# 03_-_CONTROLLER.net
KiCad netlist of a schematic drawn in Altium Designer
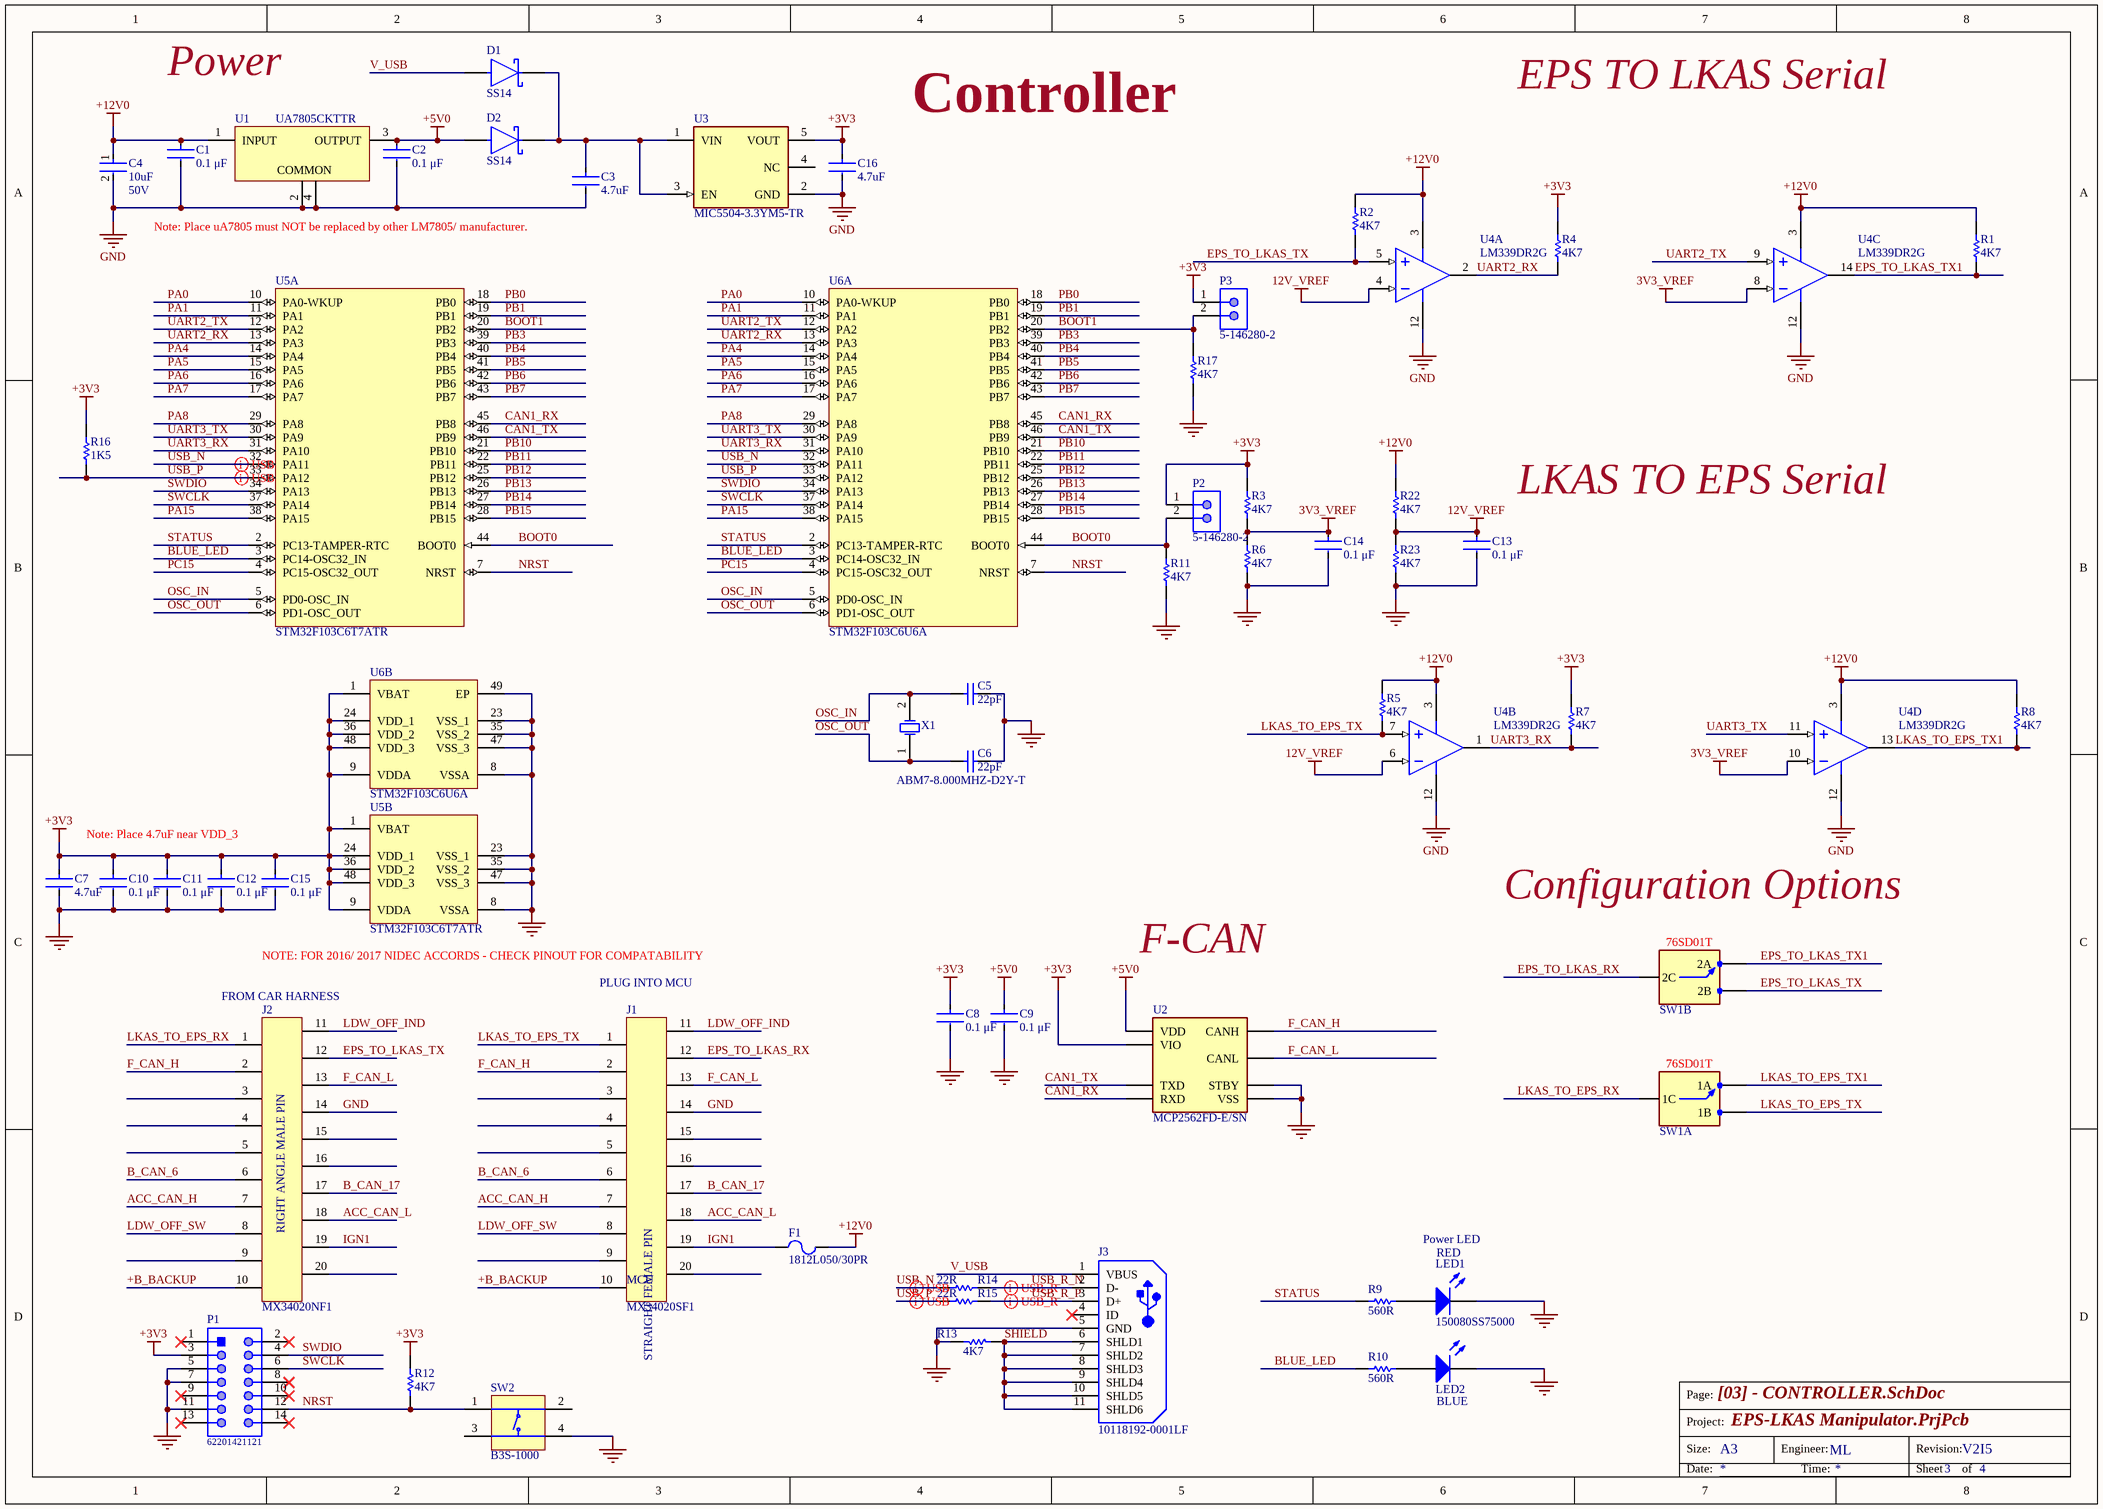
[diagram p0: [03] - CONTROLLER.SchDoc]

(export (version "E")
  (design (tool "Eeschema 10.0.6"))
  (components
    (comp (ref "C1")
      (value "C0603C104M3RACTU")
      (footprint "FP-C0603C-CF-MFG")
      (description "CAP CER 0.1UF 25V X7R 0603")
      (fields
        (field (name "CAPACITANCE") "0.1 μF")
        (field (name "OCTOPART") "https://octopart.com/c0603c104m3ractu-kemet-95914")
        (field (name "MANUFACTURER") "KEMET")
      )
      (libsource (lib "Altium Content Vault") (part "b4654b650e69147ec39a6b967a45e02"))
    )
    (comp (ref "C2")
      (value "C0603C104M3RACTU")
      (footprint "FP-C0603C-CF-MFG")
      (description "CAP CER 0.1UF 25V X7R 0603")
      (fields
        (field (name "CAPACITANCE") "0.1 μF")
        (field (name "OCTOPART") "https://octopart.com/c0603c104m3ractu-kemet-95914")
        (field (name "MANUFACTURER") "KEMET")
      )
      (libsource (lib "Altium Content Vault") (part "b4654b650e69147ec39a6b967a45e02"))
    )
    (comp (ref "C3")
      (value "CL10B475KQ8NQNC")
      (footprint "FP-CL10-IPC_C")
      (description "CAP CER 4.7UF 6.3V X7R 0603")
      (fields
        (field (name "TOLERANCE") "10%")
        (field (name "CAPACITANCE") "4.7uF")
        (field (name "OCTOPART") "https://octopart.com/cl10b475kq8nqnc-samsung-24957976")
      )
      (libsource (lib "") (part "11868f565c42a9108669ba33697ecf6_1"))
    )
    (comp (ref "C4")
      (value "10uF")
      (footprint "FP-CL31-IPC_C")
      (description "CAP CER 10UF 50V X5R 1206")
      (fields
        (field (name "TOLERANCE") "10%")
        (field (name "MANUFACTURER") "Samsung")
        (field (name "VOLTAGE") "50V")
      )
      (libsource (lib "Altium Content Vault") (part "11868f565c42a9108669ba33697ecf6"))
    )
    (comp (ref "C5")
      (value "GRM1885C1H220JA01D")
      (footprint "CAPC1608X90X35ML10T15")
      (description "Chip Capacitor, 22 pF, +/- 5%, 50 V, -55 to 125 degC, 0603 (1608 Metric), RoHS, Tape and Reel")
      (fields (field (name "CAPACITANCE") "22pF") (field (name "MANUFACTURER") "Murata"))
      (libsource (lib "Altium Content Vault") (part "CAP-NP-2"))
    )
    (comp (ref "C6")
      (value "GRM1885C1H220JA01D")
      (footprint "CAPC1608X90X35ML10T15")
      (description "Chip Capacitor, 22 pF, +/- 5%, 50 V, -55 to 125 degC, 0603 (1608 Metric), RoHS, Tape and Reel")
      (fields (field (name "CAPACITANCE") "22pF") (field (name "MANUFACTURER") "Murata"))
      (libsource (lib "Altium Content Vault") (part "CAP-NP-2"))
    )
    (comp (ref "C7")
      (value "CL10B475KQ8NQNC")
      (footprint "FP-CL10-IPC_C")
      (description "CAP CER 4.7UF 6.3V X7R 0603")
      (fields
        (field (name "TOLERANCE") "10%")
        (field (name "CAPACITANCE") "4.7uF")
        (field (name "OCTOPART") "https://octopart.com/cl10b475kq8nqnc-samsung-24957976")
      )
      (libsource (lib "") (part "11868f565c42a9108669ba33697ecf6_1"))
    )
    (comp (ref "C8")
      (value "C0603C104M3RACTU")
      (footprint "FP-C0603C-CF-MFG")
      (description "CAP CER 0.1UF 25V X7R 0603")
      (fields
        (field (name "CAPACITANCE") "0.1 μF")
        (field (name "OCTOPART") "https://octopart.com/c0603c104m3ractu-kemet-95914")
        (field (name "MANUFACTURER") "KEMET")
      )
      (libsource (lib "Altium Content Vault") (part "b4654b650e69147ec39a6b967a45e02"))
    )
    (comp (ref "C9")
      (value "C0603C104M3RACTU")
      (footprint "FP-C0603C-CF-MFG")
      (description "CAP CER 0.1UF 25V X7R 0603")
      (fields
        (field (name "CAPACITANCE") "0.1 μF")
        (field (name "OCTOPART") "https://octopart.com/c0603c104m3ractu-kemet-95914")
        (field (name "MANUFACTURER") "KEMET")
      )
      (libsource (lib "Altium Content Vault") (part "b4654b650e69147ec39a6b967a45e02"))
    )
    (comp (ref "C10")
      (value "C0603C104M3RACTU")
      (footprint "FP-C0603C-CF-MFG")
      (description "CAP CER 0.1UF 25V X7R 0603")
      (fields
        (field (name "CAPACITANCE") "0.1 μF")
        (field (name "OCTOPART") "https://octopart.com/c0603c104m3ractu-kemet-95914")
        (field (name "MANUFACTURER") "KEMET")
      )
      (libsource (lib "Altium Content Vault") (part "b4654b650e69147ec39a6b967a45e02"))
    )
    (comp (ref "C11")
      (value "C0603C104M3RACTU")
      (footprint "FP-C0603C-CF-MFG")
      (description "CAP CER 0.1UF 25V X7R 0603")
      (fields
        (field (name "CAPACITANCE") "0.1 μF")
        (field (name "OCTOPART") "https://octopart.com/c0603c104m3ractu-kemet-95914")
        (field (name "MANUFACTURER") "KEMET")
      )
      (libsource (lib "Altium Content Vault") (part "b4654b650e69147ec39a6b967a45e02"))
    )
    (comp (ref "C12")
      (value "C0603C104M3RACTU")
      (footprint "FP-C0603C-CF-MFG")
      (description "CAP CER 0.1UF 25V X7R 0603")
      (fields
        (field (name "CAPACITANCE") "0.1 μF")
        (field (name "OCTOPART") "https://octopart.com/c0603c104m3ractu-kemet-95914")
        (field (name "MANUFACTURER") "KEMET")
      )
      (libsource (lib "Altium Content Vault") (part "b4654b650e69147ec39a6b967a45e02"))
    )
    (comp (ref "C13")
      (value "C0603C104M3RACTU")
      (footprint "FP-C0603C-CF-MFG")
      (description "CAP CER 0.1UF 25V X7R 0603")
      (fields
        (field (name "CAPACITANCE") "0.1 μF")
        (field (name "OCTOPART") "https://octopart.com/c0603c104m3ractu-kemet-95914")
        (field (name "MANUFACTURER") "KEMET")
      )
      (libsource (lib "Altium Content Vault") (part "b4654b650e69147ec39a6b967a45e02"))
    )
    (comp (ref "C14")
      (value "C0603C104M3RACTU")
      (footprint "FP-C0603C-CF-MFG")
      (description "CAP CER 0.1UF 25V X7R 0603")
      (fields
        (field (name "CAPACITANCE") "0.1 μF")
        (field (name "OCTOPART") "https://octopart.com/c0603c104m3ractu-kemet-95914")
        (field (name "MANUFACTURER") "KEMET")
      )
      (libsource (lib "Altium Content Vault") (part "b4654b650e69147ec39a6b967a45e02"))
    )
    (comp (ref "C15")
      (value "C0603C104M3RACTU")
      (footprint "FP-C0603C-CF-MFG")
      (description "CAP CER 0.1UF 25V X7R 0603")
      (fields
        (field (name "CAPACITANCE") "0.1 μF")
        (field (name "OCTOPART") "https://octopart.com/c0603c104m3ractu-kemet-95914")
        (field (name "MANUFACTURER") "KEMET")
      )
      (libsource (lib "Altium Content Vault") (part "b4654b650e69147ec39a6b967a45e02"))
    )
    (comp (ref "C16")
      (value "CL10B475KQ8NQNC")
      (footprint "FP-CL10-IPC_C")
      (description "CAP CER 4.7UF 6.3V X7R 0603")
      (fields
        (field (name "TOLERANCE") "10%")
        (field (name "CAPACITANCE") "4.7uF")
        (field (name "OCTOPART") "https://octopart.com/cl10b475kq8nqnc-samsung-24957976")
      )
      (libsource (lib "") (part "11868f565c42a9108669ba33697ecf6_1"))
    )
    (comp (ref "D1")
      (value "SS14")
      (footprint "FP-403AE-MFG")
      (description "DIODE SCHOTTKY 40V 1A SMA")
      (fields
        (field (name "MANUFACTURER") "ON Semiconductor")
        (field (name "OCTOPART") "https://octopart.com/ss14-on+semiconductor-29205033")
      )
      (libsource (lib "Altium Content Vault") (part "360ad2f4ac25a952324d13796385471"))
    )
    (comp (ref "D2")
      (value "SS14")
      (footprint "FP-403AE-MFG")
      (description "DIODE SCHOTTKY 40V 1A SMA")
      (fields
        (field (name "MANUFACTURER") "ON Semiconductor")
        (field (name "OCTOPART") "https://octopart.com/ss14-on+semiconductor-29205033")
      )
      (libsource (lib "Altium Content Vault") (part "360ad2f4ac25a952324d13796385471"))
    )
    (comp (ref "F1")
      (value "1812L050/30PR")
      (footprint "LFUS-1812L05030PR_V")
      (description "PTC Resettable Fuse, 0.8 W, 30 V, -40 to 85 degC, 2-Pin SMD, RoHS, Tape and Reel")
      (fields (field (name "MANUFACTURER") "Littelfuse-Inc."))
      (libsource (lib "Altium Content Vault") (part "FUSE-2"))
    )
    (comp (ref "J1")
      (value "MX34020SF1")
      (footprint "MX34020SF1")
      (description "Automotive Connectors Sckt HOUSING 20P")
      (fields (field (name "MANUFACTURER") "JAE Electronics"))
      (libsource (lib "MCU_EPS") (part "MX34020SF1"))
    )
    (comp (ref "J2")
      (value "MX34020NF1")
      (footprint "MX34020NF1")
      (description "JAE MX34 Series, 2.2mm Pitch 20 Way 2 Row Right Angle PCB Header, Solder Termination, 3A")
      (fields (field (name "MANUFACTURER") "JAE Electronics"))
      (libsource (lib "MCU_EPS") (part "MX34020NF1"))
    )
    (comp (ref "J3")
      (value "10118192-0001LF")
      (footprint "FCI-10118192-0001LF-5_V")
      (description "Micro USB B Type Receptacle, -55 to 85 degC, 5-Pin SMD, RoHS, Tape and Reel")
      (fields (field (name "MANUFACTURER") "FCI"))
      (libsource (lib "Altium Content Vault") (part "USB-5-6SHLD"))
    )
    (comp (ref "LED1")
      (value "150080SS75000")
      (footprint "0805_A")
      (description "SMD mono-color Chip LED, WL-SMCW, Super Red")
      (fields (field (name "MANUFACTURER") "Wuerth Elektronik"))
      (libsource (lib "Altium Content Vault") (part "WE-LED_K1A2-2"))
    )
    (comp (ref "LED2")
      (value "150080BS75000")
      (footprint "0805_A")
      (description "SMD mono-color Chip LED, WL-SMCW, Blue")
      (fields (field (name "MANUFACTURER") "Wuerth Elektronik"))
      (libsource (lib "Altium Content Vault") (part "WE-LED_K1A2-2"))
    )
    (comp (ref "P1")
      (value "62201421121")
      (footprint "62201421121")
      (description "THT Vertical Pin Header WR-PHD, Pitch 1.27 mm, Dual Row, 14 pins")
      (fields (field (name "MANUFACTURER") "Wurth Elektronik") (field (name "PUBLISHER") "WurthElektronik"))
      (libsource (lib "Altium Content Vault") (part "WE-CN-2P-M-R14"))
    )
    (comp (ref "P2")
      (value "5-146280-2")
      (footprint "TECO-5-146280-2_V")
      (fields (field (name "MANUFACTURER") "TE Connectivity"))
      (libsource (lib "Altium Content Vault") (part "CN-1P-M-R2"))
    )
    (comp (ref "P3")
      (value "5-146280-2")
      (footprint "TECO-5-146280-2_V")
      (fields (field (name "MANUFACTURER") "TE Connectivity"))
      (libsource (lib "Altium Content Vault") (part "CN-1P-M-R2"))
    )
    (comp (ref "R1")
      (value "4K7")
      (footprint "R0603")
      (description "Res Thick Film 0603 4.7K Ohm 1% 1/10W 100ppm/C Molded SMD SMD Paper T/R")
      (fields
        (field (name "MANUFACTURER") "Stackpole Electronics")
        (field (name "MANUFACTURER PART NUMBER") "RMCF0603FT4K70")
      )
      (libsource (lib "LKAS_EPS") (part "RMCF0603FT4K70"))
    )
    (comp (ref "R2")
      (value "4K7")
      (footprint "R0603")
      (description "Res Thick Film 0603 4.7K Ohm 1% 1/10W 100ppm/C Molded SMD SMD Paper T/R")
      (fields
        (field (name "MANUFACTURER") "Stackpole Electronics")
        (field (name "MANUFACTURER PART NUMBER") "RMCF0603FT4K70")
      )
      (libsource (lib "LKAS_EPS") (part "RMCF0603FT4K70"))
    )
    (comp (ref "R3")
      (value "4K7")
      (footprint "R0603")
      (description "Res Thick Film 0603 4.7K Ohm 1% 1/10W 100ppm/C Molded SMD SMD Paper T/R")
      (fields
        (field (name "MANUFACTURER") "Stackpole Electronics")
        (field (name "MANUFACTURER PART NUMBER") "RMCF0603FT4K70")
      )
      (libsource (lib "LKAS_EPS") (part "RMCF0603FT4K70"))
    )
    (comp (ref "R4")
      (value "4K7")
      (footprint "R0603")
      (description "Res Thick Film 0603 4.7K Ohm 1% 1/10W 100ppm/C Molded SMD SMD Paper T/R")
      (fields
        (field (name "MANUFACTURER") "Stackpole Electronics")
        (field (name "MANUFACTURER PART NUMBER") "RMCF0603FT4K70")
      )
      (libsource (lib "LKAS_EPS") (part "RMCF0603FT4K70"))
    )
    (comp (ref "R5")
      (value "4K7")
      (footprint "R0603")
      (description "Res Thick Film 0603 4.7K Ohm 1% 1/10W 100ppm/C Molded SMD SMD Paper T/R")
      (fields
        (field (name "MANUFACTURER") "Stackpole Electronics")
        (field (name "MANUFACTURER PART NUMBER") "RMCF0603FT4K70")
      )
      (libsource (lib "LKAS_EPS") (part "RMCF0603FT4K70"))
    )
    (comp (ref "R6")
      (value "4K7")
      (footprint "R0603")
      (description "Res Thick Film 0603 4.7K Ohm 1% 1/10W 100ppm/C Molded SMD SMD Paper T/R")
      (fields
        (field (name "MANUFACTURER") "Stackpole Electronics")
        (field (name "MANUFACTURER PART NUMBER") "RMCF0603FT4K70")
      )
      (libsource (lib "LKAS_EPS") (part "RMCF0603FT4K70"))
    )
    (comp (ref "R7")
      (value "4K7")
      (footprint "R0603")
      (description "Res Thick Film 0603 4.7K Ohm 1% 1/10W 100ppm/C Molded SMD SMD Paper T/R")
      (fields
        (field (name "MANUFACTURER") "Stackpole Electronics")
        (field (name "MANUFACTURER PART NUMBER") "RMCF0603FT4K70")
      )
      (libsource (lib "LKAS_EPS") (part "RMCF0603FT4K70"))
    )
    (comp (ref "R8")
      (value "4K7")
      (footprint "R0603")
      (description "Res Thick Film 0603 4.7K Ohm 1% 1/10W 100ppm/C Molded SMD SMD Paper T/R")
      (fields
        (field (name "MANUFACTURER") "Stackpole Electronics")
        (field (name "MANUFACTURER PART NUMBER") "RMCF0603FT4K70")
      )
      (libsource (lib "LKAS_EPS") (part "RMCF0603FT4K70"))
    )
    (comp (ref "R9")
      (value "RC0603FR-07560RL")
      (footprint "RESC1608X55X25ML10T15")
      (description "Chip Resistor, 560 Ohm, +/- 1%, 0.1 W, -55 to 155 degC, 0603 (1608 Metric), RoHS, Tape and Reel")
      (fields (field (name "RESISTANCE") "560R") (field (name "TOLERANCE") "1%"))
      (libsource (lib "Altium Content Vault") (part "RES-2"))
    )
    (comp (ref "R10")
      (value "RC0603FR-07560RL")
      (footprint "RESC1608X55X25ML10T15")
      (description "Chip Resistor, 560 Ohm, +/- 1%, 0.1 W, -55 to 155 degC, 0603 (1608 Metric), RoHS, Tape and Reel")
      (fields (field (name "RESISTANCE") "560R") (field (name "TOLERANCE") "1%"))
      (libsource (lib "Altium Content Vault") (part "RES-2"))
    )
    (comp (ref "R11")
      (value "4K7")
      (footprint "R0603")
      (description "Res Thick Film 0603 4.7K Ohm 1% 1/10W 100ppm/C Molded SMD SMD Paper T/R")
      (fields
        (field (name "MANUFACTURER") "Stackpole Electronics")
        (field (name "MANUFACTURER PART NUMBER") "RMCF0603FT4K70")
      )
      (libsource (lib "LKAS_EPS") (part "RMCF0603FT4K70"))
    )
    (comp (ref "R12")
      (value "4K7")
      (footprint "R0603")
      (description "Res Thick Film 0603 4.7K Ohm 1% 1/10W 100ppm/C Molded SMD SMD Paper T/R")
      (fields
        (field (name "MANUFACTURER") "Stackpole Electronics")
        (field (name "MANUFACTURER PART NUMBER") "RMCF0603FT4K70")
      )
      (libsource (lib "LKAS_EPS") (part "RMCF0603FT4K70"))
    )
    (comp (ref "R13")
      (value "4K7")
      (footprint "R0603")
      (description "Res Thick Film 0603 4.7K Ohm 1% 1/10W 100ppm/C Molded SMD SMD Paper T/R")
      (fields
        (field (name "MANUFACTURER") "Stackpole Electronics")
        (field (name "MANUFACTURER PART NUMBER") "RMCF0603FT4K70")
      )
      (libsource (lib "LKAS_EPS") (part "RMCF0603FT4K70"))
    )
    (comp (ref "R14")
      (value "22R")
      (footprint "RESC1609X50X30ML10T20")
      (fields (field (name "MANUFACTURER") "Vishay Dale") (field (name "PART NUMBER") "CRCW060322R0JNTA"))
      (libsource (lib "Altium Content Vault") (part "RES"))
    )
    (comp (ref "R15")
      (value "22R")
      (footprint "RESC1609X50X30ML10T20")
      (fields (field (name "MANUFACTURER") "Vishay Dale") (field (name "PART NUMBER") "CRCW060322R0JNTA"))
      (libsource (lib "Altium Content Vault") (part "RES"))
    )
    (comp (ref "R16")
      (value "CRCW06031K50FKTA")
      (footprint "RESC1609X50X30ML10T20")
      (fields (field (name "MANUFACTURER") "Vishay Dale") (field (name "RES") "1K5"))
      (libsource (lib "Altium Content Vault") (part "RES"))
    )
    (comp (ref "R17")
      (value "4K7")
      (footprint "R0603")
      (description "Res Thick Film 0603 4.7K Ohm 1% 1/10W 100ppm/C Molded SMD SMD Paper T/R")
      (fields
        (field (name "MANUFACTURER") "Stackpole Electronics")
        (field (name "MANUFACTURER PART NUMBER") "RMCF0603FT4K70")
      )
      (libsource (lib "LKAS_EPS") (part "RMCF0603FT4K70"))
    )
    (comp (ref "R22")
      (value "4K7")
      (footprint "R0603")
      (description "Res Thick Film 0603 4.7K Ohm 1% 1/10W 100ppm/C Molded SMD SMD Paper T/R")
      (fields
        (field (name "MANUFACTURER") "Stackpole Electronics")
        (field (name "MANUFACTURER PART NUMBER") "RMCF0603FT4K70")
      )
      (libsource (lib "LKAS_EPS") (part "RMCF0603FT4K70"))
    )
    (comp (ref "R23")
      (value "4K7")
      (footprint "R0603")
      (description "Res Thick Film 0603 4.7K Ohm 1% 1/10W 100ppm/C Molded SMD SMD Paper T/R")
      (fields
        (field (name "MANUFACTURER") "Stackpole Electronics")
        (field (name "MANUFACTURER PART NUMBER") "RMCF0603FT4K70")
      )
      (libsource (lib "LKAS_EPS") (part "RMCF0603FT4K70"))
    )
    (comp (ref "SW1")
      (value "76STC02T")
      (footprint "76STC02T")
      (description "SWITCH TOGGLE DIP SPDT 150MA 30V\r\nWIRED:\r\n1  2  3\r\n4  5  6")
      (fields (field (name "MANUFACTURER") "Grayhill"))
      (libsource (lib "LKAS_EPS") (part "76STC02T"))
    )
    (comp (ref "SW2")
      (value "B3S-1000")
      (footprint "OMRON-B3S-1000-4_V")
      (description "Sealed Tactile Switch, SPST-NO, 3 to 24 V, -25 to 70 degC, 4-Pin SMD, RoHS, Bulk")
      (fields (field (name "MANUFACTURER") "Omron"))
      (libsource (lib "Altium Content Vault") (part "SW-SPST-4_A"))
    )
    (comp (ref "U1")
      (value "UA7805CKTTR")
      (footprint "KTT0003A_V")
      (fields (field (name "TOLERANCE") "1%"))
      (libsource (lib "Altium Content Vault") (part "TI-UA78XX-KTT-3"))
    )
    (comp (ref "U2")
      (value "MCP2562FD-E/SN")
      (footprint "MCP2561")
      (description "8 SOIC 3.90mm(.150in) TUBECAN Flexible Data Rate Transceiver")
      (fields (field (name "MANUFACTURER") "Microchip"))
      (libsource (lib "MCU_EPS") (part "MCP2562FD-E/SN"))
    )
    (comp (ref "U3")
      (value "MIC5504-3.3YM5-TR")
      (footprint "FP-SOT23-5LD-PL-1-MFG")
      (description "IC REG LINEAR 3.3V 300MA SOT23-5")
      (libsource (lib "Altium Content Vault") (part "96048095611b4a9579e1e315950d302"))
    )
    (comp (ref "U4")
      (value "LM339DR2G")
      (footprint "ONSC-SOIC-14-751A-03_V")
      (description "Single Supply Quad Comparators, 0 to 70 degC, 14-Pin SOIC, Pb-Free, Tape and Reel")
      (fields (field (name "MANUFACTURER") "On Semiconductor"))
      (libsource (lib "Altium Content Vault") (part "ONSC-LM239_LM339_LM2901_NCV2901_MC3302_LMV339-14"))
    )
    (comp (ref "U5")
      (value "STM32F103C6T7ATR")
      (footprint "STM-LQFP48_L")
      (libsource (lib "Altium Content Vault") (part "MC-ARM-STM32F103X4_6-SQ48"))
    )
    (comp (ref "U6")
      (value "STM32F103C6U6A")
      (footprint "STM-UFQFPN48_M")
      (libsource (lib "Altium Content Vault") (part "MC-ARM-STM32F103X4_6-SQ49"))
    )
    (comp (ref "X1")
      (value "ABM7-8.000MHZ-D2Y-T")
      (footprint "ABRA-ABM7-2_V")
      (description "Microprocessor Crystal, 8 MHz, 18 PF, -40 to 85 degC, 2-Pin SMD, RoHS, Tape and Reel")
      (fields (field (name "MANUFACTURER") "Abracon"))
      (libsource (lib "Altium Content Vault") (part "XTAL_1-2-2"))
    )
  )
  (nets
    (net (code "1") (name "+3V3") (class "Default")
      (node (ref "C10") (pin "1") (pinfunction "1_1") (pintype "passive"))
      (node (ref "C11") (pin "1") (pinfunction "1_1") (pintype "passive"))
      (node (ref "C12") (pin "1") (pinfunction "1_1") (pintype "passive"))
      (node (ref "C15") (pin "1") (pinfunction "1_1") (pintype "passive"))
      (node (ref "C16") (pin "1") (pinfunction "1_1") (pintype "passive"))
      (node (ref "C7") (pin "1") (pinfunction "1_1") (pintype "passive"))
      (node (ref "C8") (pin "1") (pinfunction "1_1") (pintype "passive"))
      (node (ref "P1") (pin "3") (pinfunction "3_3") (pintype "passive"))
      (node (ref "P2") (pin "1") (pinfunction "1_1") (pintype "passive"))
      (node (ref "P3") (pin "1") (pinfunction "1_1") (pintype "passive"))
      (node (ref "R12") (pin "2") (pinfunction "2_2") (pintype "passive"))
      (node (ref "R16") (pin "2") (pinfunction "2_2") (pintype "passive"))
      (node (ref "R3") (pin "2") (pinfunction "2_2") (pintype "passive"))
      (node (ref "R4") (pin "2") (pinfunction "2_2") (pintype "passive"))
      (node (ref "R7") (pin "2") (pinfunction "2_2") (pintype "passive"))
      (node (ref "U2") (pin "5") (pinfunction "VIO_5") (pintype "passive"))
      (node (ref "U3") (pin "5") (pinfunction "VOUT_5") (pintype "power_in"))
      (node (ref "U5") (pin "1") (pinfunction "VBAT_1") (pintype "power_in"))
      (node (ref "U5") (pin "24") (pinfunction "VDD_1_24") (pintype "power_in"))
      (node (ref "U5") (pin "36") (pinfunction "VDD_2_36") (pintype "power_in"))
      (node (ref "U5") (pin "48") (pinfunction "VDD_3_48") (pintype "power_in"))
      (node (ref "U5") (pin "9") (pinfunction "VDDA_9") (pintype "power_in"))
      (node (ref "U6") (pin "1") (pinfunction "VBAT_1") (pintype "power_in"))
      (node (ref "U6") (pin "24") (pinfunction "VDD_1_24") (pintype "power_in"))
      (node (ref "U6") (pin "36") (pinfunction "VDD_2_36") (pintype "power_in"))
      (node (ref "U6") (pin "48") (pinfunction "VDD_3_48") (pintype "power_in"))
      (node (ref "U6") (pin "9") (pinfunction "VDDA_9") (pintype "power_in"))
    )
    (net (code "2") (name "+5V0") (class "Default")
      (node (ref "C2") (pin "1") (pinfunction "1_1") (pintype "passive"))
      (node (ref "C9") (pin "1") (pinfunction "1_1") (pintype "passive"))
      (node (ref "D2") (pin "1") (pinfunction "A_1") (pintype "passive"))
      (node (ref "U1") (pin "3") (pinfunction "OUTPUT_3") (pintype "power_in"))
      (node (ref "U2") (pin "3") (pinfunction "VDD_3") (pintype "passive"))
    )
    (net (code "3") (name "+12V0") (class "Default")
      (node (ref "C1") (pin "1") (pinfunction "1_1") (pintype "passive"))
      (node (ref "C4") (pin "1") (pinfunction "1_1") (pintype "passive"))
      (node (ref "F1") (pin "2") (pinfunction "2_2") (pintype "passive"))
      (node (ref "R1") (pin "2") (pinfunction "2_2") (pintype "passive"))
      (node (ref "R2") (pin "2") (pinfunction "2_2") (pintype "passive"))
      (node (ref "R22") (pin "2") (pinfunction "2_2") (pintype "passive"))
      (node (ref "R5") (pin "2") (pinfunction "2_2") (pintype "passive"))
      (node (ref "R8") (pin "2") (pinfunction "2_2") (pintype "passive"))
      (node (ref "U1") (pin "1") (pinfunction "INPUT_1") (pintype "power_in"))
      (node (ref "U4") (pin "3") (pinfunction "VCC_3") (pintype "power_in"))
    )
    (net (code "4") (name "/+B_BACKUP") (class "Default")
      (node (ref "J1") (pin "10") (pinfunction "10_10") (pintype "passive"))
      (node (ref "J2") (pin "10") (pinfunction "10_10") (pintype "passive"))
    )
    (net (code "5") (name "/ACC_CAN_H") (class "Default")
      (node (ref "J1") (pin "7") (pinfunction "7_7") (pintype "passive"))
      (node (ref "J2") (pin "7") (pinfunction "7_7") (pintype "passive"))
    )
    (net (code "6") (name "/ACC_CAN_L") (class "Default")
      (node (ref "J1") (pin "18") (pinfunction "18_18") (pintype "passive"))
      (node (ref "J2") (pin "18") (pinfunction "18_18") (pintype "passive"))
    )
    (net (code "7") (name "/BLUE_LED") (class "Default")
      (node (ref "R10") (pin "1") (pinfunction "1_1") (pintype "passive"))
      (node (ref "U5") (pin "3") (pinfunction "PC14-OSC32_IN_3") (pintype "bidirectional"))
      (node (ref "U6") (pin "3") (pinfunction "PC14-OSC32_IN_3") (pintype "bidirectional"))
    )
    (net (code "8") (name "/BOOT0") (class "Default")
      (node (ref "P2") (pin "2") (pinfunction "2_2") (pintype "passive"))
      (node (ref "R11") (pin "2") (pinfunction "2_2") (pintype "passive"))
      (node (ref "U5") (pin "44") (pinfunction "BOOT0_44") (pintype "input"))
      (node (ref "U6") (pin "44") (pinfunction "BOOT0_44") (pintype "input"))
    )
    (net (code "9") (name "/BOOT1") (class "Default")
      (node (ref "P3") (pin "2") (pinfunction "2_2") (pintype "passive"))
      (node (ref "R17") (pin "2") (pinfunction "2_2") (pintype "passive"))
      (node (ref "U5") (pin "20") (pinfunction "PB2_20") (pintype "bidirectional"))
      (node (ref "U6") (pin "20") (pinfunction "PB2_20") (pintype "bidirectional"))
    )
    (net (code "10") (name "/B_CAN_6") (class "Default")
      (node (ref "J1") (pin "6") (pinfunction "6_6") (pintype "passive"))
      (node (ref "J2") (pin "6") (pinfunction "6_6") (pintype "passive"))
    )
    (net (code "11") (name "/B_CAN_17") (class "Default")
      (node (ref "J1") (pin "17") (pinfunction "17_17") (pintype "passive"))
      (node (ref "J2") (pin "17") (pinfunction "17_17") (pintype "passive"))
    )
    (net (code "12") (name "/CAN1_RX") (class "Default")
      (node (ref "U2") (pin "4") (pinfunction "RXD_4") (pintype "passive"))
      (node (ref "U5") (pin "45") (pinfunction "PB8_45") (pintype "bidirectional"))
      (node (ref "U6") (pin "45") (pinfunction "PB8_45") (pintype "bidirectional"))
    )
    (net (code "13") (name "/CAN1_TX") (class "Default")
      (node (ref "U2") (pin "1") (pinfunction "TXD_1") (pintype "passive"))
      (node (ref "U5") (pin "46") (pinfunction "PB9_46") (pintype "bidirectional"))
      (node (ref "U6") (pin "46") (pinfunction "PB9_46") (pintype "bidirectional"))
    )
    (net (code "14") (name "/EPS_TO_LKAS_RX") (class "Default")
      (node (ref "J1") (pin "12") (pinfunction "12_12") (pintype "passive"))
      (node (ref "SW1") (pin "C2") (pinfunction "2C_C2") (pintype "passive"))
    )
    (net (code "15") (name "/EPS_TO_LKAS_TX") (class "Default")
      (node (ref "J2") (pin "12") (pinfunction "12_12") (pintype "passive"))
      (node (ref "R2") (pin "1") (pinfunction "1_1") (pintype "passive"))
      (node (ref "SW1") (pin "2B") (pinfunction "2B_2B") (pintype "passive"))
      (node (ref "U4") (pin "5") (pinfunction "IN1+_5") (pintype "input"))
    )
    (net (code "16") (name "/EPS_TO_LKAS_TX1") (class "Default")
      (node (ref "R1") (pin "1") (pinfunction "1_1") (pintype "passive"))
      (node (ref "SW1") (pin "2A") (pinfunction "2A_2A") (pintype "passive"))
      (node (ref "U4") (pin "14") (pinfunction "OUT3_14") (pintype "open_collector"))
    )
    (net (code "17") (name "/F_CAN_H") (class "Default")
      (node (ref "J1") (pin "2") (pinfunction "2_2") (pintype "passive"))
      (node (ref "J2") (pin "2") (pinfunction "2_2") (pintype "passive"))
      (node (ref "U2") (pin "7") (pinfunction "CANH_7") (pintype "passive"))
    )
    (net (code "18") (name "/F_CAN_L") (class "Default")
      (node (ref "J1") (pin "13") (pinfunction "13_13") (pintype "passive"))
      (node (ref "J2") (pin "13") (pinfunction "13_13") (pintype "passive"))
      (node (ref "U2") (pin "6") (pinfunction "CANL_6") (pintype "passive"))
    )
    (net (code "19") (name "/IGN1") (class "Default")
      (node (ref "F1") (pin "1") (pinfunction "1_1") (pintype "passive"))
      (node (ref "J1") (pin "19") (pinfunction "19_19") (pintype "passive"))
      (node (ref "J2") (pin "19") (pinfunction "19_19") (pintype "passive"))
    )
    (net (code "20") (name "/LDW_OFF_IND") (class "Default")
      (node (ref "J1") (pin "11") (pinfunction "11_11") (pintype "passive"))
      (node (ref "J2") (pin "11") (pinfunction "11_11") (pintype "passive"))
    )
    (net (code "21") (name "/LDW_OFF_SW") (class "Default")
      (node (ref "J1") (pin "8") (pinfunction "8_8") (pintype "passive"))
      (node (ref "J2") (pin "8") (pinfunction "8_8") (pintype "passive"))
    )
    (net (code "22") (name "/LKAS_TO_EPS_RX") (class "Default")
      (node (ref "J2") (pin "1") (pinfunction "1_1") (pintype "passive"))
      (node (ref "SW1") (pin "C1") (pinfunction "1C_C1") (pintype "passive"))
    )
    (net (code "23") (name "/LKAS_TO_EPS_TX") (class "Default")
      (node (ref "J1") (pin "1") (pinfunction "1_1") (pintype "passive"))
      (node (ref "R5") (pin "1") (pinfunction "1_1") (pintype "passive"))
      (node (ref "SW1") (pin "1B") (pinfunction "1B_1B") (pintype "passive"))
      (node (ref "U4") (pin "7") (pinfunction "IN2+_7") (pintype "input"))
    )
    (net (code "24") (name "/LKAS_TO_EPS_TX1") (class "Default")
      (node (ref "R8") (pin "1") (pinfunction "1_1") (pintype "passive"))
      (node (ref "SW1") (pin "1A") (pinfunction "1A_1A") (pintype "passive"))
      (node (ref "U4") (pin "13") (pinfunction "OUT4_13") (pintype "open_collector"))
    )
    (net (code "25") (name "/NRST") (class "Default")
      (node (ref "P1") (pin "12") (pinfunction "12_12") (pintype "passive"))
      (node (ref "R12") (pin "1") (pinfunction "1_1") (pintype "passive"))
      (node (ref "SW2") (pin "1") (pinfunction "1_1") (pintype "passive"))
      (node (ref "U5") (pin "7") (pinfunction "NRST_7") (pintype "bidirectional"))
      (node (ref "U6") (pin "7") (pinfunction "NRST_7") (pintype "bidirectional"))
    )
    (net (code "26") (name "/OSC_IN") (class "Default")
      (node (ref "C5") (pin "1") (pinfunction "1_1") (pintype "passive"))
      (node (ref "U5") (pin "5") (pinfunction "PD0-OSC_IN_5") (pintype "bidirectional"))
      (node (ref "U6") (pin "5") (pinfunction "PD0-OSC_IN_5") (pintype "bidirectional"))
      (node (ref "X1") (pin "2") (pinfunction "X2_2") (pintype "passive"))
    )
    (net (code "27") (name "/OSC_OUT") (class "Default")
      (node (ref "C6") (pin "1") (pinfunction "1_1") (pintype "passive"))
      (node (ref "U5") (pin "6") (pinfunction "PD1-OSC_OUT_6") (pintype "bidirectional"))
      (node (ref "U6") (pin "6") (pinfunction "PD1-OSC_OUT_6") (pintype "bidirectional"))
      (node (ref "X1") (pin "1") (pinfunction "X1_1") (pintype "passive"))
    )
    (net (code "28") (name "/PA0") (class "Default")
      (node (ref "U5") (pin "10") (pinfunction "PA0-WKUP_10") (pintype "bidirectional"))
      (node (ref "U6") (pin "10") (pinfunction "PA0-WKUP_10") (pintype "bidirectional"))
    )
    (net (code "29") (name "/PA1") (class "Default")
      (node (ref "U5") (pin "11") (pinfunction "PA1_11") (pintype "bidirectional"))
      (node (ref "U6") (pin "11") (pinfunction "PA1_11") (pintype "bidirectional"))
    )
    (net (code "30") (name "/PA4") (class "Default")
      (node (ref "U5") (pin "14") (pinfunction "PA4_14") (pintype "bidirectional"))
      (node (ref "U6") (pin "14") (pinfunction "PA4_14") (pintype "bidirectional"))
    )
    (net (code "31") (name "/PA5") (class "Default")
      (node (ref "U5") (pin "15") (pinfunction "PA5_15") (pintype "bidirectional"))
      (node (ref "U6") (pin "15") (pinfunction "PA5_15") (pintype "bidirectional"))
    )
    (net (code "32") (name "/PA6") (class "Default")
      (node (ref "U5") (pin "16") (pinfunction "PA6_16") (pintype "bidirectional"))
      (node (ref "U6") (pin "16") (pinfunction "PA6_16") (pintype "bidirectional"))
    )
    (net (code "33") (name "/PA7") (class "Default")
      (node (ref "U5") (pin "17") (pinfunction "PA7_17") (pintype "bidirectional"))
      (node (ref "U6") (pin "17") (pinfunction "PA7_17") (pintype "bidirectional"))
    )
    (net (code "34") (name "/PA8") (class "Default")
      (node (ref "U5") (pin "29") (pinfunction "PA8_29") (pintype "bidirectional"))
      (node (ref "U6") (pin "29") (pinfunction "PA8_29") (pintype "bidirectional"))
    )
    (net (code "35") (name "/PA15") (class "Default")
      (node (ref "U5") (pin "38") (pinfunction "PA15_38") (pintype "bidirectional"))
      (node (ref "U6") (pin "38") (pinfunction "PA15_38") (pintype "bidirectional"))
    )
    (net (code "36") (name "/PB0") (class "Default")
      (node (ref "U5") (pin "18") (pinfunction "PB0_18") (pintype "bidirectional"))
      (node (ref "U6") (pin "18") (pinfunction "PB0_18") (pintype "bidirectional"))
    )
    (net (code "37") (name "/PB1") (class "Default")
      (node (ref "U5") (pin "19") (pinfunction "PB1_19") (pintype "bidirectional"))
      (node (ref "U6") (pin "19") (pinfunction "PB1_19") (pintype "bidirectional"))
    )
    (net (code "38") (name "/PB3") (class "Default")
      (node (ref "U5") (pin "39") (pinfunction "PB3_39") (pintype "bidirectional"))
      (node (ref "U6") (pin "39") (pinfunction "PB3_39") (pintype "bidirectional"))
    )
    (net (code "39") (name "/PB4") (class "Default")
      (node (ref "U5") (pin "40") (pinfunction "PB4_40") (pintype "bidirectional"))
      (node (ref "U6") (pin "40") (pinfunction "PB4_40") (pintype "bidirectional"))
    )
    (net (code "40") (name "/PB5") (class "Default")
      (node (ref "U5") (pin "41") (pinfunction "PB5_41") (pintype "bidirectional"))
      (node (ref "U6") (pin "41") (pinfunction "PB5_41") (pintype "bidirectional"))
    )
    (net (code "41") (name "/PB6") (class "Default")
      (node (ref "U5") (pin "42") (pinfunction "PB6_42") (pintype "bidirectional"))
      (node (ref "U6") (pin "42") (pinfunction "PB6_42") (pintype "bidirectional"))
    )
    (net (code "42") (name "/PB7") (class "Default")
      (node (ref "U5") (pin "43") (pinfunction "PB7_43") (pintype "bidirectional"))
      (node (ref "U6") (pin "43") (pinfunction "PB7_43") (pintype "bidirectional"))
    )
    (net (code "43") (name "/PB10") (class "Default")
      (node (ref "U5") (pin "21") (pinfunction "PB10_21") (pintype "bidirectional"))
      (node (ref "U6") (pin "21") (pinfunction "PB10_21") (pintype "bidirectional"))
    )
    (net (code "44") (name "/PB11") (class "Default")
      (node (ref "U5") (pin "22") (pinfunction "PB11_22") (pintype "bidirectional"))
      (node (ref "U6") (pin "22") (pinfunction "PB11_22") (pintype "bidirectional"))
    )
    (net (code "45") (name "/PB12") (class "Default")
      (node (ref "U5") (pin "25") (pinfunction "PB12_25") (pintype "bidirectional"))
      (node (ref "U6") (pin "25") (pinfunction "PB12_25") (pintype "bidirectional"))
    )
    (net (code "46") (name "/PB13") (class "Default")
      (node (ref "U5") (pin "26") (pinfunction "PB13_26") (pintype "bidirectional"))
      (node (ref "U6") (pin "26") (pinfunction "PB13_26") (pintype "bidirectional"))
    )
    (net (code "47") (name "/PB14") (class "Default")
      (node (ref "U5") (pin "27") (pinfunction "PB14_27") (pintype "bidirectional"))
      (node (ref "U6") (pin "27") (pinfunction "PB14_27") (pintype "bidirectional"))
    )
    (net (code "48") (name "/PB15") (class "Default")
      (node (ref "U5") (pin "28") (pinfunction "PB15_28") (pintype "bidirectional"))
      (node (ref "U6") (pin "28") (pinfunction "PB15_28") (pintype "bidirectional"))
    )
    (net (code "49") (name "/PC15") (class "Default")
      (node (ref "U5") (pin "4") (pinfunction "PC15-OSC32_OUT_4") (pintype "bidirectional"))
      (node (ref "U6") (pin "4") (pinfunction "PC15-OSC32_OUT_4") (pintype "bidirectional"))
    )
    (net (code "50") (name "/SHIELD") (class "Default")
      (node (ref "J3") (pin "10") (pinfunction "SHLD5_10") (pintype "passive"))
      (node (ref "J3") (pin "11") (pinfunction "SHLD6_11") (pintype "passive"))
      (node (ref "J3") (pin "6") (pinfunction "SHLD1_6") (pintype "passive"))
      (node (ref "J3") (pin "7") (pinfunction "SHLD2_7") (pintype "passive"))
      (node (ref "J3") (pin "8") (pinfunction "SHLD3_8") (pintype "passive"))
      (node (ref "J3") (pin "9") (pinfunction "SHLD4_9") (pintype "passive"))
      (node (ref "R13") (pin "1") (pinfunction "1_1") (pintype "passive"))
    )
    (net (code "51") (name "/STATUS") (class "Default")
      (node (ref "R9") (pin "1") (pinfunction "1_1") (pintype "passive"))
      (node (ref "U5") (pin "2") (pinfunction "PC13-TAMPER-RTC_2") (pintype "bidirectional"))
      (node (ref "U6") (pin "2") (pinfunction "PC13-TAMPER-RTC_2") (pintype "bidirectional"))
    )
    (net (code "52") (name "/SWCLK") (class "Default")
      (node (ref "P1") (pin "6") (pinfunction "6_6") (pintype "passive"))
      (node (ref "U5") (pin "37") (pinfunction "PA14_37") (pintype "bidirectional"))
      (node (ref "U6") (pin "37") (pinfunction "PA14_37") (pintype "bidirectional"))
    )
    (net (code "53") (name "/SWDIO") (class "Default")
      (node (ref "P1") (pin "4") (pinfunction "4_4") (pintype "passive"))
      (node (ref "U5") (pin "34") (pinfunction "PA13_34") (pintype "bidirectional"))
      (node (ref "U6") (pin "34") (pinfunction "PA13_34") (pintype "bidirectional"))
    )
    (net (code "54") (name "/UART2_RX") (class "Default")
      (node (ref "R4") (pin "1") (pinfunction "1_1") (pintype "passive"))
      (node (ref "U4") (pin "2") (pinfunction "OUT1_2") (pintype "open_collector"))
      (node (ref "U5") (pin "13") (pinfunction "PA3_13") (pintype "bidirectional"))
      (node (ref "U6") (pin "13") (pinfunction "PA3_13") (pintype "bidirectional"))
    )
    (net (code "55") (name "/UART2_TX") (class "Default")
      (node (ref "U4") (pin "9") (pinfunction "IN3+_9") (pintype "input"))
      (node (ref "U5") (pin "12") (pinfunction "PA2_12") (pintype "bidirectional"))
      (node (ref "U6") (pin "12") (pinfunction "PA2_12") (pintype "bidirectional"))
    )
    (net (code "56") (name "/UART3_RX") (class "Default")
      (node (ref "R7") (pin "1") (pinfunction "1_1") (pintype "passive"))
      (node (ref "U4") (pin "1") (pinfunction "OUT2_1") (pintype "open_collector"))
      (node (ref "U5") (pin "31") (pinfunction "PA10_31") (pintype "bidirectional"))
      (node (ref "U6") (pin "31") (pinfunction "PA10_31") (pintype "bidirectional"))
    )
    (net (code "57") (name "/UART3_TX") (class "Default")
      (node (ref "U4") (pin "11") (pinfunction "IN4+_11") (pintype "input"))
      (node (ref "U5") (pin "30") (pinfunction "PA9_30") (pintype "bidirectional"))
      (node (ref "U6") (pin "30") (pinfunction "PA9_30") (pintype "bidirectional"))
    )
    (net (code "58") (name "/USB_N") (class "Default")
      (node (ref "R14") (pin "1") (pinfunction "1_1") (pintype "passive"))
      (node (ref "U5") (pin "32") (pinfunction "PA11_32") (pintype "bidirectional"))
      (node (ref "U6") (pin "32") (pinfunction "PA11_32") (pintype "bidirectional"))
    )
    (net (code "59") (name "/USB_P") (class "Default")
      (node (ref "R15") (pin "1") (pinfunction "1_1") (pintype "passive"))
      (node (ref "R16") (pin "1") (pinfunction "1_1") (pintype "passive"))
      (node (ref "U5") (pin "33") (pinfunction "PA12_33") (pintype "bidirectional"))
      (node (ref "U6") (pin "33") (pinfunction "PA12_33") (pintype "bidirectional"))
    )
    (net (code "60") (name "/USB_R_N") (class "Default")
      (node (ref "J3") (pin "2") (pinfunction "D-_2") (pintype "passive"))
      (node (ref "R14") (pin "2") (pinfunction "2_2") (pintype "passive"))
    )
    (net (code "61") (name "/USB_R_P") (class "Default")
      (node (ref "J3") (pin "3") (pinfunction "D+_3") (pintype "passive"))
      (node (ref "R15") (pin "2") (pinfunction "2_2") (pintype "passive"))
    )
    (net (code "62") (name "/V_USB") (class "Default")
      (node (ref "D1") (pin "1") (pinfunction "A_1") (pintype "passive"))
      (node (ref "J3") (pin "1") (pinfunction "VBUS_1") (pintype "passive"))
    )
    (net (code "63") (name "3V3_VREF") (class "Default")
      (node (ref "C14") (pin "1") (pinfunction "1_1") (pintype "passive"))
      (node (ref "R3") (pin "1") (pinfunction "1_1") (pintype "passive"))
      (node (ref "R6") (pin "2") (pinfunction "2_2") (pintype "passive"))
      (node (ref "U4") (pin "10") (pinfunction "IN4-_10") (pintype "input"))
      (node (ref "U4") (pin "8") (pinfunction "IN3-_8") (pintype "input"))
    )
    (net (code "64") (name "12V_VREF") (class "Default")
      (node (ref "C13") (pin "1") (pinfunction "1_1") (pintype "passive"))
      (node (ref "R22") (pin "1") (pinfunction "1_1") (pintype "passive"))
      (node (ref "R23") (pin "2") (pinfunction "2_2") (pintype "passive"))
      (node (ref "U4") (pin "4") (pinfunction "IN1-_4") (pintype "input"))
      (node (ref "U4") (pin "6") (pinfunction "IN2-_6") (pintype "input"))
    )
    (net (code "65") (name "GND") (class "Default")
      (node (ref "C1") (pin "2") (pinfunction "2_2") (pintype "passive"))
      (node (ref "C10") (pin "2") (pinfunction "2_2") (pintype "passive"))
      (node (ref "C11") (pin "2") (pinfunction "2_2") (pintype "passive"))
      (node (ref "C12") (pin "2") (pinfunction "2_2") (pintype "passive"))
      (node (ref "C13") (pin "2") (pinfunction "2_2") (pintype "passive"))
      (node (ref "C14") (pin "2") (pinfunction "2_2") (pintype "passive"))
      (node (ref "C15") (pin "2") (pinfunction "2_2") (pintype "passive"))
      (node (ref "C16") (pin "2") (pinfunction "2_2") (pintype "passive"))
      (node (ref "C2") (pin "2") (pinfunction "2_2") (pintype "passive"))
      (node (ref "C3") (pin "2") (pinfunction "2_2") (pintype "passive"))
      (node (ref "C4") (pin "2") (pinfunction "2_2") (pintype "passive"))
      (node (ref "C5") (pin "2") (pinfunction "2_2") (pintype "passive"))
      (node (ref "C6") (pin "2") (pinfunction "2_2") (pintype "passive"))
      (node (ref "C7") (pin "2") (pinfunction "2_2") (pintype "passive"))
      (node (ref "C8") (pin "2") (pinfunction "2_2") (pintype "passive"))
      (node (ref "C9") (pin "2") (pinfunction "2_2") (pintype "passive"))
      (node (ref "J1") (pin "14") (pinfunction "14_14") (pintype "passive"))
      (node (ref "J2") (pin "14") (pinfunction "14_14") (pintype "passive"))
      (node (ref "J3") (pin "5") (pinfunction "GND_5") (pintype "passive"))
      (node (ref "LED1") (pin "1") (pinfunction "K_1") (pintype "passive"))
      (node (ref "LED2") (pin "1") (pinfunction "K_1") (pintype "passive"))
      (node (ref "P1") (pin "11") (pinfunction "11_11") (pintype "passive"))
      (node (ref "P1") (pin "5") (pinfunction "5_5") (pintype "passive"))
      (node (ref "P1") (pin "7") (pinfunction "7_7") (pintype "passive"))
      (node (ref "R11") (pin "1") (pinfunction "1_1") (pintype "passive"))
      (node (ref "R13") (pin "2") (pinfunction "2_2") (pintype "passive"))
      (node (ref "R17") (pin "1") (pinfunction "1_1") (pintype "passive"))
      (node (ref "R23") (pin "1") (pinfunction "1_1") (pintype "passive"))
      (node (ref "R6") (pin "1") (pinfunction "1_1") (pintype "passive"))
      (node (ref "SW2") (pin "4") (pinfunction "4_4") (pintype "passive"))
      (node (ref "U1") (pin "2") (pinfunction "COMMON_2") (pintype "power_in"))
      (node (ref "U1") (pin "4") (pinfunction "COMMON_4") (pintype "power_in"))
      (node (ref "U2") (pin "2") (pinfunction "VSS_2") (pintype "passive"))
      (node (ref "U2") (pin "8") (pinfunction "STBY_8") (pintype "passive"))
      (node (ref "U3") (pin "2") (pinfunction "GND_2") (pintype "power_in"))
      (node (ref "U4") (pin "12") (pinfunction "GND_12") (pintype "power_in"))
      (node (ref "U5") (pin "23") (pinfunction "VSS_1_23") (pintype "power_in"))
      (node (ref "U5") (pin "35") (pinfunction "VSS_2_35") (pintype "power_in"))
      (node (ref "U5") (pin "47") (pinfunction "VSS_3_47") (pintype "power_in"))
      (node (ref "U5") (pin "8") (pinfunction "VSSA_8") (pintype "power_in"))
      (node (ref "U6") (pin "23") (pinfunction "VSS_1_23") (pintype "power_in"))
      (node (ref "U6") (pin "35") (pinfunction "VSS_2_35") (pintype "power_in"))
      (node (ref "U6") (pin "47") (pinfunction "VSS_3_47") (pintype "power_in"))
      (node (ref "U6") (pin "49") (pinfunction "EP_49") (pintype "power_in"))
      (node (ref "U6") (pin "8") (pinfunction "VSSA_8") (pintype "power_in"))
    )
    (net (code "66") (name "Net-(D1-C)") (class "Default")
      (node (ref "C3") (pin "1") (pinfunction "1_1") (pintype "passive"))
      (node (ref "D1") (pin "2") (pinfunction "C_2") (pintype "passive"))
      (node (ref "D2") (pin "2") (pinfunction "C_2") (pintype "passive"))
      (node (ref "U3") (pin "1") (pinfunction "VIN_1") (pintype "power_in"))
      (node (ref "U3") (pin "3") (pinfunction "EN_3") (pintype "input"))
    )
    (net (code "67") (name "Net-(LED1-A)") (class "Default")
      (node (ref "LED1") (pin "2") (pinfunction "A_2") (pintype "passive"))
      (node (ref "R9") (pin "2") (pinfunction "2_2") (pintype "passive"))
    )
    (net (code "68") (name "Net-(LED2-A)") (class "Default")
      (node (ref "LED2") (pin "2") (pinfunction "A_2") (pintype "passive"))
      (node (ref "R10") (pin "2") (pinfunction "2_2") (pintype "passive"))
    )
    (net (code "69") (name "unconnected-(J1-Pad3)") (class "Default")
      (node (ref "J1") (pin "3") (pinfunction "3_3") (pintype "passive"))
    )
    (net (code "70") (name "unconnected-(J1-Pad4)") (class "Default")
      (node (ref "J1") (pin "4") (pinfunction "4_4") (pintype "passive"))
    )
    (net (code "71") (name "unconnected-(J1-Pad5)") (class "Default")
      (node (ref "J1") (pin "5") (pinfunction "5_5") (pintype "passive"))
    )
    (net (code "72") (name "unconnected-(J1-Pad9)") (class "Default")
      (node (ref "J1") (pin "9") (pinfunction "9_9") (pintype "passive"))
    )
    (net (code "73") (name "unconnected-(J1-Pad15)") (class "Default")
      (node (ref "J1") (pin "15") (pinfunction "15_15") (pintype "passive"))
    )
    (net (code "74") (name "unconnected-(J1-Pad16)") (class "Default")
      (node (ref "J1") (pin "16") (pinfunction "16_16") (pintype "passive"))
    )
    (net (code "75") (name "unconnected-(J1-Pad20)") (class "Default")
      (node (ref "J1") (pin "20") (pinfunction "20_20") (pintype "passive"))
    )
    (net (code "76") (name "unconnected-(J2-Pad3)") (class "Default")
      (node (ref "J2") (pin "3") (pinfunction "3_3") (pintype "passive"))
    )
    (net (code "77") (name "unconnected-(J2-Pad4)") (class "Default")
      (node (ref "J2") (pin "4") (pinfunction "4_4") (pintype "passive"))
    )
    (net (code "78") (name "unconnected-(J2-Pad5)") (class "Default")
      (node (ref "J2") (pin "5") (pinfunction "5_5") (pintype "passive"))
    )
    (net (code "79") (name "unconnected-(J2-Pad9)") (class "Default")
      (node (ref "J2") (pin "9") (pinfunction "9_9") (pintype "passive"))
    )
    (net (code "80") (name "unconnected-(J2-Pad15)") (class "Default")
      (node (ref "J2") (pin "15") (pinfunction "15_15") (pintype "passive"))
    )
    (net (code "81") (name "unconnected-(J2-Pad16)") (class "Default")
      (node (ref "J2") (pin "16") (pinfunction "16_16") (pintype "passive"))
    )
    (net (code "82") (name "unconnected-(J2-Pad20)") (class "Default")
      (node (ref "J2") (pin "20") (pinfunction "20_20") (pintype "passive"))
    )
    (net (code "83") (name "unconnected-(J3-ID-Pad4)") (class "Default")
      (node (ref "J3") (pin "4") (pinfunction "ID_4") (pintype "passive+no_connect"))
    )
    (net (code "84") (name "unconnected-(P1-Pad1)") (class "Default")
      (node (ref "P1") (pin "1") (pinfunction "1_1") (pintype "passive+no_connect"))
    )
    (net (code "85") (name "unconnected-(P1-Pad2)") (class "Default")
      (node (ref "P1") (pin "2") (pinfunction "2_2") (pintype "passive+no_connect"))
    )
    (net (code "86") (name "unconnected-(P1-Pad8)") (class "Default")
      (node (ref "P1") (pin "8") (pinfunction "8_8") (pintype "passive+no_connect"))
    )
    (net (code "87") (name "unconnected-(P1-Pad9)") (class "Default")
      (node (ref "P1") (pin "9") (pinfunction "9_9") (pintype "passive+no_connect"))
    )
    (net (code "88") (name "unconnected-(P1-Pad10)") (class "Default")
      (node (ref "P1") (pin "10") (pinfunction "10_10") (pintype "passive+no_connect"))
    )
    (net (code "89") (name "unconnected-(P1-Pad13)") (class "Default")
      (node (ref "P1") (pin "13") (pinfunction "13_13") (pintype "passive+no_connect"))
    )
    (net (code "90") (name "unconnected-(P1-Pad14)") (class "Default")
      (node (ref "P1") (pin "14") (pinfunction "14_14") (pintype "passive+no_connect"))
    )
    (net (code "91") (name "unconnected-(SW2-Pad2)") (class "Default")
      (node (ref "SW2") (pin "2") (pinfunction "2_2") (pintype "passive"))
    )
    (net (code "92") (name "unconnected-(SW2-Pad3)") (class "Default")
      (node (ref "SW2") (pin "3") (pinfunction "3_3") (pintype "passive"))
    )
    (net (code "93") (name "unconnected-(U3-NC-Pad4)") (class "Default")
      (node (ref "U3") (pin "4") (pinfunction "NC_4") (pintype "passive"))
    )
  )
)
